# Simple-Bug-2N918.net
KiCad netlist of a schematic drawn in EAGLE
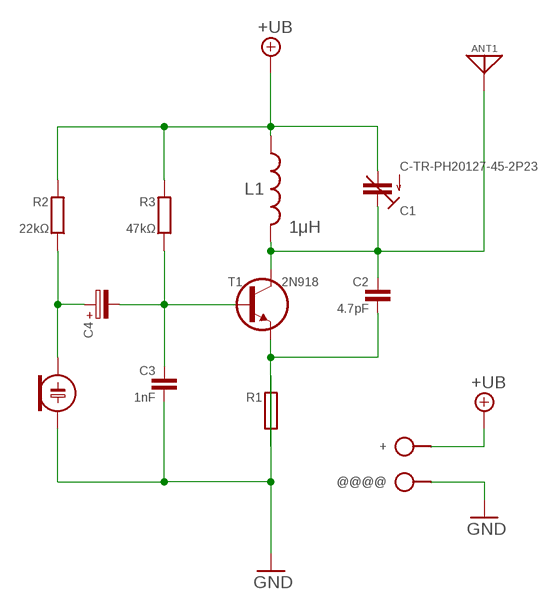
[diagram p0: schematic, sheet 1]

(export (version "E")
  (design (tool "Eeschema 10.0.6"))
  (components
    (comp (ref "+")
      (value "SPAD")
      (footprint "eagle-import:SPAD")
      (libsource (lib "eagle-import") (part "SPAD"))
    )
    (comp (ref "@@@@")
      (value "SPAD")
      (footprint "eagle-import:SPAD")
      (libsource (lib "eagle-import") (part "SPAD"))
    )
    (comp (ref "ANT1")
      (value "ANT")
      (footprint "eagle-import:SPAD")
      (libsource (lib "eagle-import") (part "ANT"))
    )
    (comp (ref "C1")
      (value "C-TR-PH20127-45-2P23")
      (footprint "eagle-import:TRIM808-45")
      (libsource (lib "eagle-import") (part "C-TR-PH20127-45-2P21"))
    )
    (comp (ref "C2")
      (value "4.7pF")
      (footprint "eagle-import:C025-020X036")
      (libsource (lib "eagle-import") (part "C025-020X036"))
    )
    (comp (ref "C3")
      (value "1nF")
      (footprint "eagle-import:C025-020X036")
      (libsource (lib "eagle-import") (part "C025-020X036"))
    )
    (comp (ref "C4")
      (value "CPOLE2,5-3")
      (footprint "eagle-import:E2,5-3")
      (libsource (lib "eagle-import") (part "CPOLE2,5-3"))
    )
    (comp (ref "ECM")
      (value "ECM-5")
      (footprint "eagle-import:ECM-5")
      (libsource (lib "eagle-import") (part "ECM-5"))
    )
    (comp (ref "L1")
      (value "1μH")
      (footprint "eagle-import:L-04_7")
      (libsource (lib "eagle-import") (part "L04/7"))
    )
    (comp (ref "R1")
      (value "R0202V")
      (footprint "eagle-import:0202V")
      (libsource (lib "eagle-import") (part "R0202V"))
    )
    (comp (ref "R2")
      (value "22kΩ")
      (footprint "eagle-import:0202_5")
      (libsource (lib "eagle-import") (part "R0202/5"))
    )
    (comp (ref "R3")
      (value "47kΩ")
      (footprint "eagle-import:0202_5")
      (libsource (lib "eagle-import") (part "R0202/5"))
    )
    (comp (ref "T1")
      (value "2N918")
      (footprint "eagle-import:TO72-A45")
      (libsource (lib "eagle-import") (part "2N918TO-72-A45"))
    )
  )
  (nets
    (net (code "1") (name "+UB") (class "Default")
      (node (ref "+") (pin "1") (pinfunction "P$1_1") (pintype "passive"))
      (node (ref "C1") (pin "1") (pinfunction "A_1") (pintype "passive"))
      (node (ref "L1") (pin "1") (pinfunction "1_1") (pintype "passive"))
      (node (ref "R2") (pin "1") (pinfunction "1_1") (pintype "passive"))
      (node (ref "R3") (pin "1") (pinfunction "1_1") (pintype "passive"))
    )
    (net (code "2") (name "GND") (class "Default")
      (node (ref "@@@@") (pin "1") (pinfunction "P$1_1") (pintype "passive"))
      (node (ref "C3") (pin "2") (pinfunction "2_2") (pintype "passive"))
      (node (ref "ECM") (pin "1") (pinfunction "+_1") (pintype "passive"))
      (node (ref "R1") (pin "1") (pinfunction "1_1") (pintype "passive"))
    )
    (net (code "3") (name "Net-(C1-E)") (class "Default")
      (node (ref "ANT1") (pin "1") (pinfunction "1_1") (pintype "output"))
      (node (ref "C1") (pin "2") (pinfunction "E_2") (pintype "passive"))
      (node (ref "C2") (pin "1") (pinfunction "1_1") (pintype "passive"))
      (node (ref "L1") (pin "2") (pinfunction "2_2") (pintype "passive"))
      (node (ref "T1") (pin "3") (pinfunction "C_3") (pintype "passive"))
    )
    (net (code "4") (name "Net-(ECM--)") (class "Default")
      (node (ref "C4") (pin "+") (pinfunction "+_+") (pintype "passive"))
      (node (ref "ECM") (pin "2") (pinfunction "-_2") (pintype "passive"))
      (node (ref "R2") (pin "2") (pinfunction "2_2") (pintype "passive"))
    )
    (net (code "5") (name "Net-(T1-B)") (class "Default")
      (node (ref "C3") (pin "1") (pinfunction "1_1") (pintype "passive"))
      (node (ref "C4") (pin "-") (pinfunction "-_-") (pintype "passive"))
      (node (ref "R3") (pin "2") (pinfunction "2_2") (pintype "passive"))
      (node (ref "T1") (pin "2") (pinfunction "B_2") (pintype "passive"))
    )
    (net (code "6") (name "Net-(T1-E)") (class "Default")
      (node (ref "C2") (pin "2") (pinfunction "2_2") (pintype "passive"))
      (node (ref "R1") (pin "2") (pinfunction "2_2") (pintype "passive"))
      (node (ref "T1") (pin "1") (pinfunction "E_1") (pintype "passive"))
    )
  )
)
